# SCH3_Main_Computer_Eth.net
KiCad netlist of a schematic drawn in Altium Designer
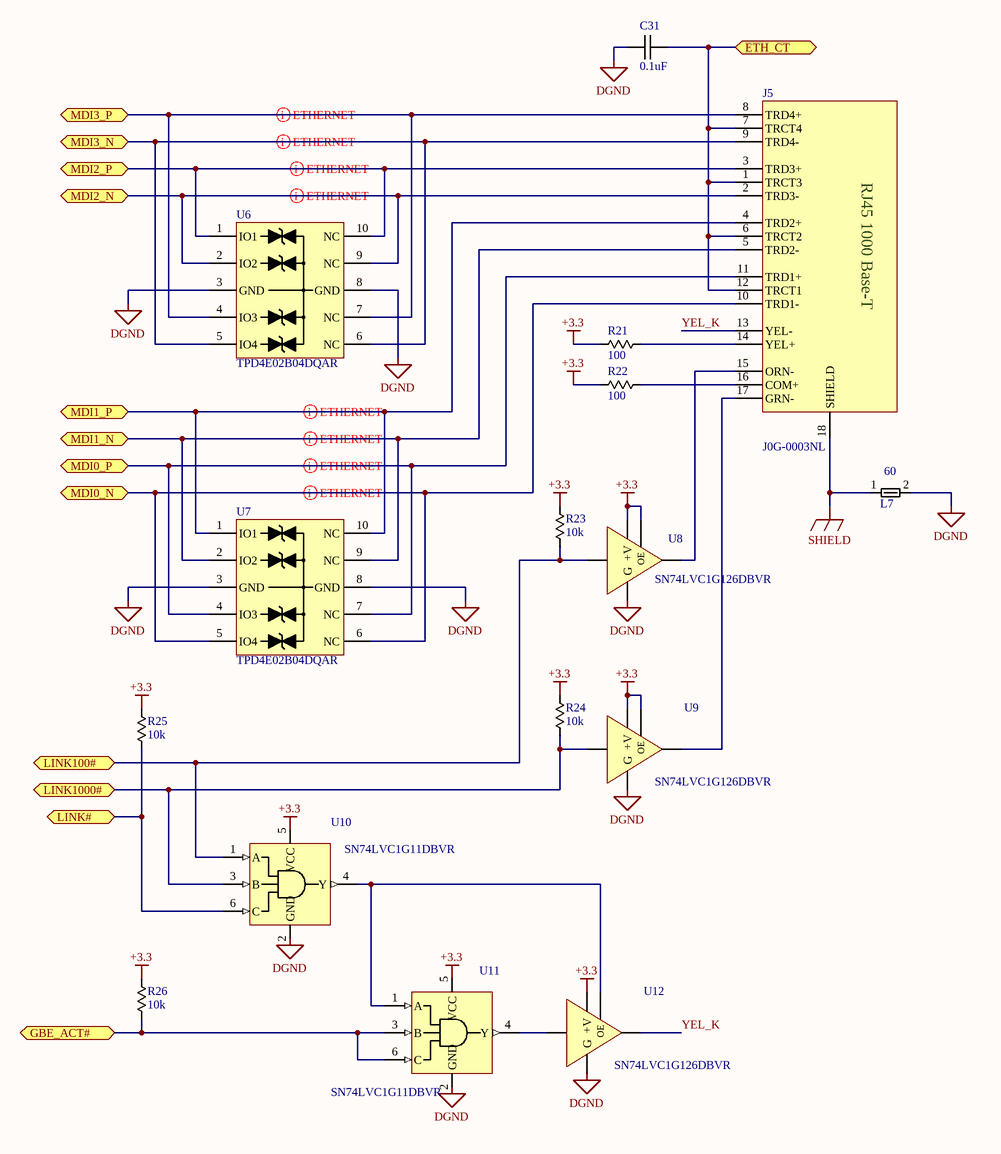
[diagram p0: SCH3_Main_Computer_Eth.SchDoc]

(export (version "E")
  (design (tool "Eeschema 10.0.6"))
  (components
    (comp (ref "C31")
      (value "0.1uF")
      (footprint "chip_0603")
      (description "CAP, 0.1uF, ±10%, 16V, X7R, 0603")
      (fields (field (name "PART NUMBER") "CAP-00542") (field (name "TOLERANCE") "±10%"))
      (libsource (lib "Capacitors$") (part "CAP-00542"))
    )
    (comp (ref "J5")
      (value "J0G-0003NL")
      (footprint "J0G-0003NL")
      (description "RJ45 Modular Mag-jack, 8P8C, 1000 Base-T, Horizontal")
      (fields
        (field (name "PART NUMBER") "CONN-00082")
        (field (name "MANUFACTURER") "Pulse Electronics Network")
      )
      (libsource (lib "Connectors$") (part "CONN-00082"))
    )
    (comp (ref "L7")
      (value "bead_0")
      (footprint "CHIP_0805_FE")
      (description "Fe Bead, 60 @ 100MH, 3A, 0805")
      (fields
        (field (name "PART NUMBER") "MAG-00125")
        (field (name "IMPEDANCE") "60")
        (field (name "MANUFACTURER") "Pulse Electronics")
      )
      (libsource (lib "Magnetics$") (part "MAG-00125"))
    )
    (comp (ref "R21")
      (value "100")
      (footprint "chip_0603")
      (description "RES SMD 100 OHM 1% 1/4W 0603")
      (fields (field (name "PART NUMBER") "RES-00178") (field (name "TOLERANCE") "1%"))
      (libsource (lib "Resistors$") (part "RES-00178"))
    )
    (comp (ref "R22")
      (value "100")
      (footprint "chip_0603")
      (description "RES SMD 100 OHM 1% 1/4W 0603")
      (fields (field (name "PART NUMBER") "RES-00178") (field (name "TOLERANCE") "1%"))
      (libsource (lib "Resistors$") (part "RES-00178"))
    )
    (comp (ref "R23")
      (value "10k")
      (footprint "chip_0603")
      (description "RES SMD 10K OHM 1% 1/4W 0603")
      (fields (field (name "PART NUMBER") "RES-00306") (field (name "TOLERANCE") "1%"))
      (libsource (lib "Resistors$") (part "RES-00306"))
    )
    (comp (ref "R24")
      (value "10k")
      (footprint "chip_0603")
      (description "RES SMD 10K OHM 1% 1/4W 0603")
      (fields (field (name "PART NUMBER") "RES-00306") (field (name "TOLERANCE") "1%"))
      (libsource (lib "Resistors$") (part "RES-00306"))
    )
    (comp (ref "R25")
      (value "10k")
      (footprint "chip_0603")
      (description "RES SMD 10K OHM 1% 1/4W 0603")
      (fields (field (name "PART NUMBER") "RES-00306") (field (name "TOLERANCE") "1%"))
      (libsource (lib "Resistors$") (part "RES-00306"))
    )
    (comp (ref "R26")
      (value "10k")
      (footprint "chip_0603")
      (description "RES SMD 10K OHM 1% 1/4W 0603")
      (fields (field (name "PART NUMBER") "RES-00306") (field (name "TOLERANCE") "1%"))
      (libsource (lib "Resistors$") (part "RES-00306"))
    )
    (comp (ref "U6")
      (value "TPD4E02B04DQAR")
      (footprint "USON-10")
      (description "TVS, 4-Ch, ESD Protec, 3.6V 8.8V 10-USON")
      (fields (field (name "PART NUMBER") "DIO-00068") (field (name "MANUFACTURER") "TI"))
      (libsource (lib "Diodes$") (part "DIO-00068"))
    )
    (comp (ref "U7")
      (value "TPD4E02B04DQAR")
      (footprint "USON-10")
      (description "TVS, 4-Ch, ESD Protec, 3.6V 8.8V 10-USON")
      (fields (field (name "PART NUMBER") "DIO-00068") (field (name "MANUFACTURER") "TI"))
      (libsource (lib "Diodes$") (part "DIO-00068"))
    )
    (comp (ref "U8")
      (value "SN74LVC1G126DBVR")
      (footprint "sot-23-5")
      (description "IC, Tri-State Buffer Non-Inverting, Single, 1.65-5.5V, SOT-23-5")
      (fields (field (name "PART NUMBER") "LOGIC-00040") (field (name "MANUFACTURER") "TI"))
      (libsource (lib "Logic$") (part "LOGIC-00040"))
    )
    (comp (ref "U9")
      (value "SN74LVC1G126DBVR")
      (footprint "sot-23-5")
      (description "IC, Tri-State Buffer Non-Inverting, Single, 1.65-5.5V, SOT-23-5")
      (fields (field (name "PART NUMBER") "LOGIC-00040") (field (name "MANUFACTURER") "TI"))
      (libsource (lib "Logic$") (part "LOGIC-00040"))
    )
    (comp (ref "U10")
      (value "SN74LVC1G11DBVR")
      (footprint "sot-23-6")
      (description "IC, AND Gate, Single 3-Input, 1.65-5.5V, SOT-23-6")
      (fields (field (name "PART NUMBER") "LOGIC-00042") (field (name "MANUFACTURER") "TI"))
      (libsource (lib "Logic$") (part "LOGIC-00042"))
    )
    (comp (ref "U11")
      (value "SN74LVC1G11DBVR")
      (footprint "sot-23-6")
      (description "IC, AND Gate, Single 3-Input, 1.65-5.5V, SOT-23-6")
      (fields (field (name "PART NUMBER") "LOGIC-00042") (field (name "MANUFACTURER") "TI"))
      (libsource (lib "Logic$") (part "LOGIC-00042"))
    )
    (comp (ref "U12")
      (value "SN74LVC1G126DBVR")
      (footprint "sot-23-5")
      (description "IC, Tri-State Buffer Non-Inverting, Single, 1.65-5.5V, SOT-23-5")
      (fields (field (name "PART NUMBER") "LOGIC-00040") (field (name "MANUFACTURER") "TI"))
      (libsource (lib "Logic$") (part "LOGIC-00040"))
    )
  )
  (nets
    (net (code "1") (name "+3.3") (class "Default")
      (node (ref "R21") (pin "1") (pinfunction "1_1") (pintype "passive"))
      (node (ref "R22") (pin "1") (pinfunction "1_1") (pintype "passive"))
      (node (ref "R23") (pin "1") (pinfunction "1_1") (pintype "passive"))
      (node (ref "R24") (pin "1") (pinfunction "1_1") (pintype "passive"))
      (node (ref "R25") (pin "1") (pinfunction "1_1") (pintype "passive"))
      (node (ref "R26") (pin "1") (pinfunction "1_1") (pintype "passive"))
      (node (ref "U10") (pin "5") (pinfunction "VCC_5") (pintype "power_in"))
      (node (ref "U11") (pin "5") (pinfunction "VCC_5") (pintype "power_in"))
      (node (ref "U12") (pin "5") (pinfunction "+V_5") (pintype "passive"))
      (node (ref "U8") (pin "1") (pinfunction "OE_1") (pintype "passive"))
      (node (ref "U8") (pin "5") (pinfunction "+V_5") (pintype "passive"))
      (node (ref "U9") (pin "1") (pinfunction "OE_1") (pintype "passive"))
      (node (ref "U9") (pin "5") (pinfunction "+V_5") (pintype "passive"))
    )
    (net (code "2") (name "/ETH_CT") (class "Default")
      (node (ref "C31") (pin "2") (pinfunction "2_2") (pintype "passive"))
      (node (ref "J5") (pin "1") (pinfunction "TRCT3_1") (pintype "passive"))
      (node (ref "J5") (pin "12") (pinfunction "TRCT1_12") (pintype "passive"))
      (node (ref "J5") (pin "6") (pinfunction "TRCT2_6") (pintype "passive"))
      (node (ref "J5") (pin "7") (pinfunction "TRCT4_7") (pintype "passive"))
    )
    (net (code "3") (name "/GBE_ACT#") (class "Default")
      (node (ref "R26") (pin "2") (pinfunction "2_2") (pintype "passive"))
      (node (ref "U11") (pin "3") (pinfunction "B_3") (pintype "input"))
      (node (ref "U11") (pin "6") (pinfunction "C_6") (pintype "input"))
    )
    (net (code "4") (name "/LINK#") (class "Default")
      (node (ref "R25") (pin "2") (pinfunction "2_2") (pintype "passive"))
      (node (ref "U10") (pin "6") (pinfunction "C_6") (pintype "input"))
    )
    (net (code "5") (name "/LINK100#") (class "Default")
      (node (ref "R23") (pin "2") (pinfunction "2_2") (pintype "passive"))
      (node (ref "U10") (pin "1") (pinfunction "A_1") (pintype "input"))
      (node (ref "U8") (pin "2") (pinfunction "A_2") (pintype "passive"))
    )
    (net (code "6") (name "/LINK1000#") (class "Default")
      (node (ref "R24") (pin "2") (pinfunction "2_2") (pintype "passive"))
      (node (ref "U10") (pin "3") (pinfunction "B_3") (pintype "input"))
      (node (ref "U9") (pin "2") (pinfunction "A_2") (pintype "passive"))
    )
    (net (code "7") (name "/MDI0_N") (class "Default")
      (node (ref "J5") (pin "10") (pinfunction "TRD1-_10") (pintype "passive"))
      (node (ref "U7") (pin "5") (pinfunction "IO4_5") (pintype "passive"))
      (node (ref "U7") (pin "6") (pinfunction "NC_6") (pintype "passive"))
    )
    (net (code "8") (name "/MDI0_P") (class "Default")
      (node (ref "J5") (pin "11") (pinfunction "TRD1+_11") (pintype "passive"))
      (node (ref "U7") (pin "4") (pinfunction "IO3_4") (pintype "passive"))
      (node (ref "U7") (pin "7") (pinfunction "NC_7") (pintype "passive"))
    )
    (net (code "9") (name "/MDI1_N") (class "Default")
      (node (ref "J5") (pin "5") (pinfunction "TRD2-_5") (pintype "passive"))
      (node (ref "U7") (pin "2") (pinfunction "IO2_2") (pintype "passive"))
      (node (ref "U7") (pin "9") (pinfunction "NC_9") (pintype "passive"))
    )
    (net (code "10") (name "/MDI1_P") (class "Default")
      (node (ref "J5") (pin "4") (pinfunction "TRD2+_4") (pintype "passive"))
      (node (ref "U7") (pin "1") (pinfunction "IO1_1") (pintype "passive"))
      (node (ref "U7") (pin "10") (pinfunction "NC_10") (pintype "passive"))
    )
    (net (code "11") (name "/MDI2_N") (class "Default")
      (node (ref "J5") (pin "2") (pinfunction "TRD3-_2") (pintype "passive"))
      (node (ref "U6") (pin "2") (pinfunction "IO2_2") (pintype "passive"))
      (node (ref "U6") (pin "9") (pinfunction "NC_9") (pintype "passive"))
    )
    (net (code "12") (name "/MDI2_P") (class "Default")
      (node (ref "J5") (pin "3") (pinfunction "TRD3+_3") (pintype "passive"))
      (node (ref "U6") (pin "1") (pinfunction "IO1_1") (pintype "passive"))
      (node (ref "U6") (pin "10") (pinfunction "NC_10") (pintype "passive"))
    )
    (net (code "13") (name "/MDI3_N") (class "Default")
      (node (ref "J5") (pin "9") (pinfunction "TRD4-_9") (pintype "passive"))
      (node (ref "U6") (pin "5") (pinfunction "IO4_5") (pintype "passive"))
      (node (ref "U6") (pin "6") (pinfunction "NC_6") (pintype "passive"))
    )
    (net (code "14") (name "/MDI3_P") (class "Default")
      (node (ref "J5") (pin "8") (pinfunction "TRD4+_8") (pintype "passive"))
      (node (ref "U6") (pin "4") (pinfunction "IO3_4") (pintype "passive"))
      (node (ref "U6") (pin "7") (pinfunction "NC_7") (pintype "passive"))
    )
    (net (code "15") (name "/YEL_K") (class "Default")
      (node (ref "J5") (pin "13") (pinfunction "YEL-_13") (pintype "passive"))
      (node (ref "U12") (pin "4") (pinfunction "Y_4") (pintype "passive"))
    )
    (net (code "16") (name "DGND") (class "Default")
      (node (ref "C31") (pin "1") (pinfunction "1_1") (pintype "passive"))
      (node (ref "L7") (pin "2") (pinfunction "2_2") (pintype "passive"))
      (node (ref "U10") (pin "2") (pinfunction "GND_2") (pintype "power_in"))
      (node (ref "U11") (pin "2") (pinfunction "GND_2") (pintype "power_in"))
      (node (ref "U12") (pin "3") (pinfunction "G_3") (pintype "passive"))
      (node (ref "U6") (pin "3") (pinfunction "GND_3") (pintype "passive"))
      (node (ref "U6") (pin "8") (pinfunction "GND_8") (pintype "passive"))
      (node (ref "U7") (pin "3") (pinfunction "GND_3") (pintype "passive"))
      (node (ref "U7") (pin "8") (pinfunction "GND_8") (pintype "passive"))
      (node (ref "U8") (pin "3") (pinfunction "G_3") (pintype "passive"))
      (node (ref "U9") (pin "3") (pinfunction "G_3") (pintype "passive"))
    )
    (net (code "17") (name "Net-(J5-COM+)") (class "Default")
      (node (ref "J5") (pin "16") (pinfunction "COM+_16") (pintype "passive"))
      (node (ref "R22") (pin "2") (pinfunction "2_2") (pintype "passive"))
    )
    (net (code "18") (name "Net-(J5-GRN-)") (class "Default")
      (node (ref "J5") (pin "17") (pinfunction "GRN-_17") (pintype "passive"))
      (node (ref "U9") (pin "4") (pinfunction "Y_4") (pintype "passive"))
    )
    (net (code "19") (name "Net-(J5-ORN-)") (class "Default")
      (node (ref "J5") (pin "15") (pinfunction "ORN-_15") (pintype "passive"))
      (node (ref "U8") (pin "4") (pinfunction "Y_4") (pintype "passive"))
    )
    (net (code "20") (name "Net-(J5-YEL+)") (class "Default")
      (node (ref "J5") (pin "14") (pinfunction "YEL+_14") (pintype "passive"))
      (node (ref "R21") (pin "2") (pinfunction "2_2") (pintype "passive"))
    )
    (net (code "21") (name "Net-(U10-Y)") (class "Default")
      (node (ref "U10") (pin "4") (pinfunction "Y_4") (pintype "output"))
      (node (ref "U11") (pin "1") (pinfunction "A_1") (pintype "input"))
      (node (ref "U12") (pin "1") (pinfunction "OE_1") (pintype "passive"))
    )
    (net (code "22") (name "Net-(U11-Y)") (class "Default")
      (node (ref "U11") (pin "4") (pinfunction "Y_4") (pintype "output"))
      (node (ref "U12") (pin "2") (pinfunction "A_2") (pintype "passive"))
    )
    (net (code "23") (name "SHIELD") (class "Default")
      (node (ref "J5") (pin "18") (pinfunction "SHIELD_18") (pintype "passive"))
      (node (ref "L7") (pin "1") (pinfunction "1_1") (pintype "passive"))
    )
  )
)
